# PowerBoard.net
KiCad netlist of a schematic drawn in EAGLE
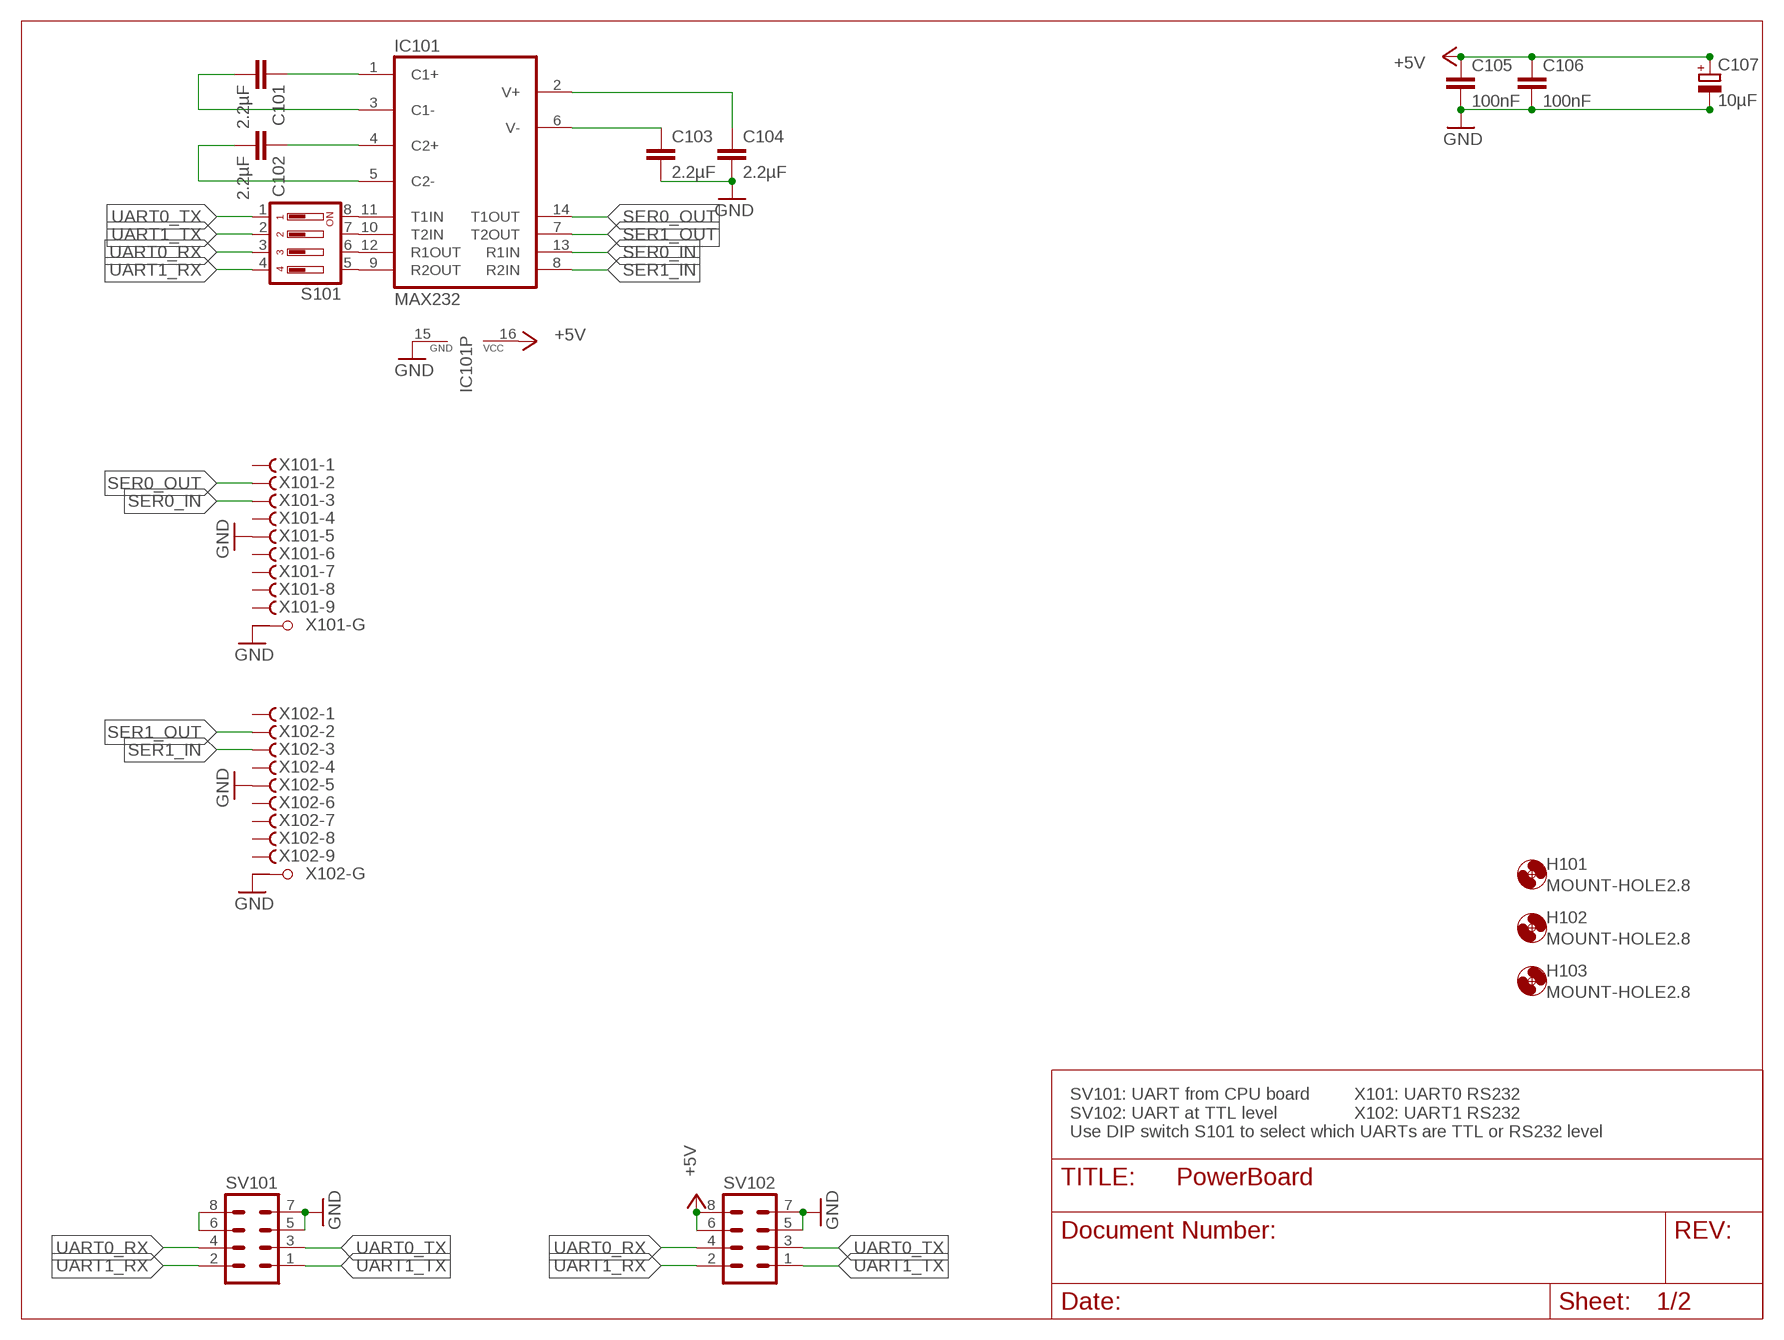
[diagram p0: schematic, sheet 1]
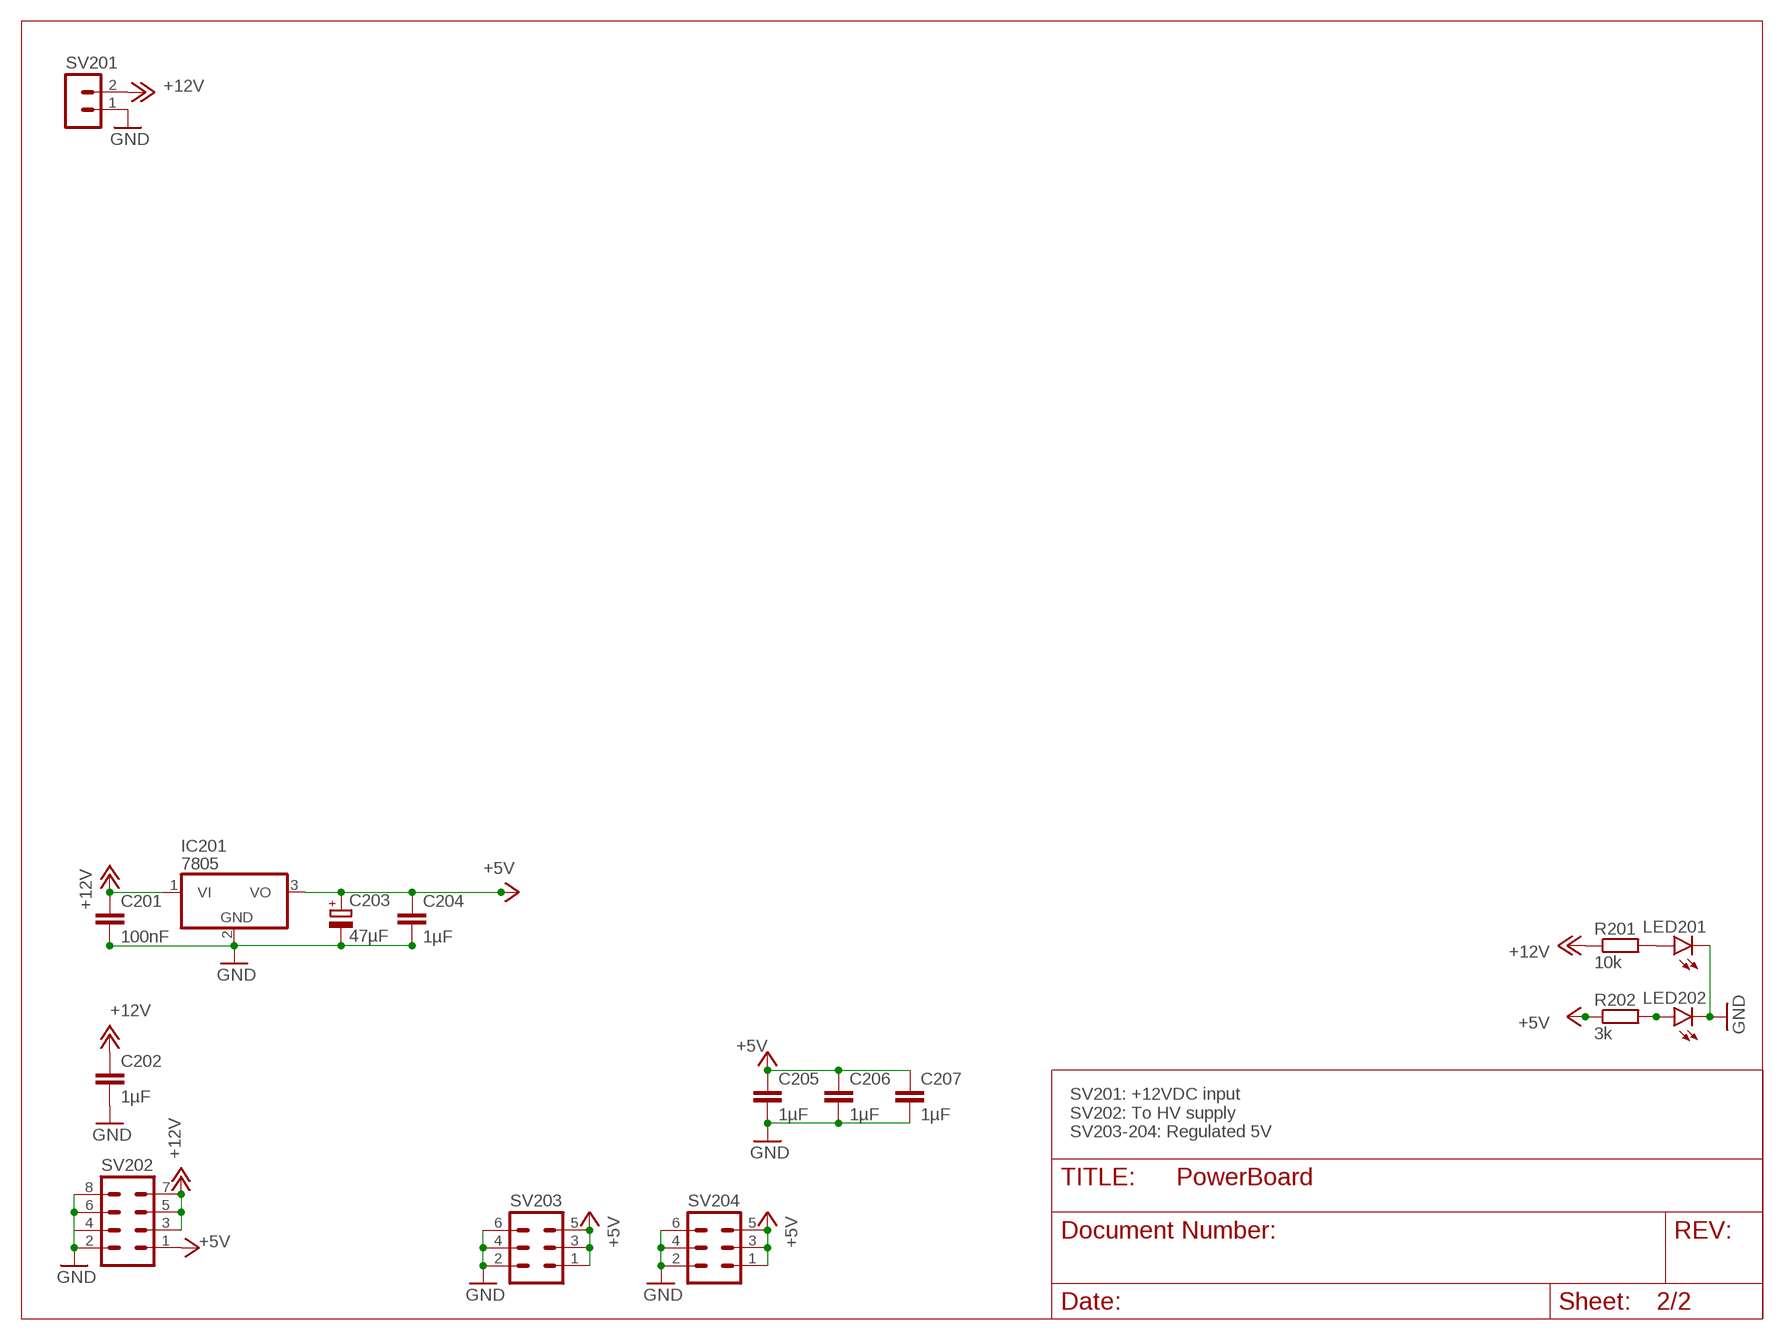
[diagram p1: schematic, sheet 2]

(export (version "E")
  (design (tool "Eeschema 10.0.6"))
  (components
    (comp (ref "C101")
      (value "2.2µF")
      (footprint "eagle-import:C0805")
      (libsource (lib "eagle-import") (part "C-EUC0805"))
    )
    (comp (ref "C102")
      (value "2.2µF")
      (footprint "eagle-import:C0805")
      (libsource (lib "eagle-import") (part "C-EUC0805"))
    )
    (comp (ref "C103")
      (value "2.2µF")
      (footprint "eagle-import:C0805")
      (libsource (lib "eagle-import") (part "C-EUC0805"))
    )
    (comp (ref "C104")
      (value "2.2µF")
      (footprint "eagle-import:C0805")
      (libsource (lib "eagle-import") (part "C-EUC0805"))
    )
    (comp (ref "C105")
      (value "100nF")
      (footprint "eagle-import:C0805")
      (libsource (lib "eagle-import") (part "C-EUC0805"))
    )
    (comp (ref "C106")
      (value "100nF")
      (footprint "eagle-import:C0805")
      (libsource (lib "eagle-import") (part "C-EUC0805"))
    )
    (comp (ref "C107")
      (value "10µF")
      (footprint "eagle-import:SMC_B")
      (libsource (lib "eagle-import") (part "CPOL-EUSMCB"))
    )
    (comp (ref "H101")
      (value "MOUNT-HOLE2.8")
      (footprint "eagle-import:2,8")
      (libsource (lib "eagle-import") (part "MOUNT-HOLE2.8"))
    )
    (comp (ref "H102")
      (value "MOUNT-HOLE2.8")
      (footprint "eagle-import:2,8")
      (libsource (lib "eagle-import") (part "MOUNT-HOLE2.8"))
    )
    (comp (ref "H103")
      (value "MOUNT-HOLE2.8")
      (footprint "eagle-import:2,8")
      (libsource (lib "eagle-import") (part "MOUNT-HOLE2.8"))
    )
    (comp (ref "IC101")
      (value "MAX232")
      (footprint "eagle-import:DIL16")
      (fields
        (field (name "MF") "MAXIM")
        (field (name "MPN") "MAX232ACPE+")
        (field (name "MOUSER") "595-MAX232N")
      )
      (libsource (lib "eagle-import") (part "MAX232"))
    )
    (comp (ref "S101")
      (value "DP04")
      (footprint "eagle-import:DP-04")
      (libsource (lib "eagle-import") (part "DP04"))
    )
    (comp (ref "SV101")
      (value "MA04-2")
      (footprint "eagle-import:MA04-2")
      (libsource (lib "eagle-import") (part "MA04-2"))
    )
    (comp (ref "SV102")
      (value "MA04-2")
      (footprint "eagle-import:MA04-2")
      (libsource (lib "eagle-import") (part "MA04-2"))
    )
    (comp (ref "X101")
      (value "F09HPS")
      (footprint "eagle-import:F09HP")
      (libsource (lib "eagle-import") (part "F09HPS"))
    )
    (comp (ref "X102")
      (value "F09HPS")
      (footprint "eagle-import:F09HP")
      (libsource (lib "eagle-import") (part "F09HPS"))
    )
    (comp (ref "C201")
      (value "100nF")
      (footprint "eagle-import:C0805")
      (libsource (lib "eagle-import") (part "C-EUC0805"))
    )
    (comp (ref "C202")
      (value "1µF")
      (footprint "eagle-import:C0805")
      (libsource (lib "eagle-import") (part "C-EUC0805"))
    )
    (comp (ref "C203")
      (value "47µF")
      (footprint "eagle-import:CT6032")
      (libsource (lib "eagle-import") (part "CPOL-EUCT6032"))
    )
    (comp (ref "C204")
      (value "1µF")
      (footprint "eagle-import:C0805")
      (libsource (lib "eagle-import") (part "C-EUC0805"))
    )
    (comp (ref "C205")
      (value "1µF")
      (footprint "eagle-import:C0805")
      (libsource (lib "eagle-import") (part "C-EUC0805"))
    )
    (comp (ref "C206")
      (value "1µF")
      (footprint "eagle-import:C0805")
      (libsource (lib "eagle-import") (part "C-EUC0805"))
    )
    (comp (ref "C207")
      (value "1µF")
      (footprint "eagle-import:C0805")
      (libsource (lib "eagle-import") (part "C-EUC0805"))
    )
    (comp (ref "IC201")
      (value "7805")
      (footprint "eagle-import:TO220V")
      (libsource (lib "eagle-import") (part "78TV05"))
    )
    (comp (ref "LED201")
      (value "LEDCHIPLED_1206")
      (footprint "eagle-import:CHIPLED_1206")
      (libsource (lib "eagle-import") (part "LEDCHIPLED_1206"))
    )
    (comp (ref "LED202")
      (value "LEDCHIPLED_1206")
      (footprint "eagle-import:CHIPLED_1206")
      (libsource (lib "eagle-import") (part "LEDCHIPLED_1206"))
    )
    (comp (ref "R201")
      (value "10k")
      (footprint "eagle-import:R2012")
      (libsource (lib "eagle-import") (part "R-EU_R2012"))
    )
    (comp (ref "R202")
      (value "3k")
      (footprint "eagle-import:R2012")
      (libsource (lib "eagle-import") (part "R-EU_R2012"))
    )
    (comp (ref "SV201")
      (value "1792863")
      (footprint "eagle-import:1792863")
      (libsource (lib "eagle-import") (part "1792863"))
    )
    (comp (ref "SV202")
      (value "MA04-2")
      (footprint "eagle-import:MA04-2")
      (libsource (lib "eagle-import") (part "MA04-2"))
    )
    (comp (ref "SV203")
      (value "MA03-2")
      (footprint "eagle-import:MA03-2")
      (libsource (lib "eagle-import") (part "MA03-2"))
    )
    (comp (ref "SV204")
      (value "MA03-2")
      (footprint "eagle-import:MA03-2")
      (libsource (lib "eagle-import") (part "MA03-2"))
    )
  )
  (nets
    (net (code "1") (name "+5V") (class "Default")
      (node (ref "C105") (pin "1") (pinfunction "1_1") (pintype "passive"))
      (node (ref "C106") (pin "1") (pinfunction "1_1") (pintype "passive"))
      (node (ref "C107") (pin "+") (pinfunction "+_+") (pintype "passive"))
      (node (ref "C203") (pin "+") (pinfunction "+_+") (pintype "passive"))
      (node (ref "C204") (pin "1") (pinfunction "1_1") (pintype "passive"))
      (node (ref "C205") (pin "1") (pinfunction "1_1") (pintype "passive"))
      (node (ref "C206") (pin "1") (pinfunction "1_1") (pintype "passive"))
      (node (ref "C207") (pin "1") (pinfunction "1_1") (pintype "passive"))
      (node (ref "IC101") (pin "16") (pinfunction "VCC_16") (pintype "power_in"))
      (node (ref "IC201") (pin "3") (pinfunction "VO_3") (pintype "passive"))
      (node (ref "R202") (pin "1") (pinfunction "1_1") (pintype "passive"))
      (node (ref "SV102") (pin "6") (pinfunction "6_6") (pintype "passive"))
      (node (ref "SV102") (pin "8") (pinfunction "8_8") (pintype "passive"))
      (node (ref "SV202") (pin "1") (pinfunction "1_1") (pintype "passive"))
      (node (ref "SV203") (pin "1") (pinfunction "1_1") (pintype "passive"))
      (node (ref "SV203") (pin "3") (pinfunction "3_3") (pintype "passive"))
      (node (ref "SV203") (pin "5") (pinfunction "5_5") (pintype "passive"))
      (node (ref "SV204") (pin "1") (pinfunction "1_1") (pintype "passive"))
      (node (ref "SV204") (pin "3") (pinfunction "3_3") (pintype "passive"))
      (node (ref "SV204") (pin "5") (pinfunction "5_5") (pintype "passive"))
    )
    (net (code "2") (name "+12V") (class "Default")
      (node (ref "C201") (pin "1") (pinfunction "1_1") (pintype "passive"))
      (node (ref "C202") (pin "1") (pinfunction "1_1") (pintype "passive"))
      (node (ref "IC201") (pin "1") (pinfunction "VI_1") (pintype "input"))
      (node (ref "R201") (pin "1") (pinfunction "1_1") (pintype "passive"))
      (node (ref "SV201") (pin "2") (pinfunction "2_2") (pintype "passive"))
      (node (ref "SV202") (pin "3") (pinfunction "3_3") (pintype "passive"))
      (node (ref "SV202") (pin "5") (pinfunction "5_5") (pintype "passive"))
      (node (ref "SV202") (pin "7") (pinfunction "7_7") (pintype "passive"))
    )
    (net (code "3") (name "GND") (class "Default")
      (node (ref "C103") (pin "2") (pinfunction "2_2") (pintype "passive"))
      (node (ref "C104") (pin "2") (pinfunction "2_2") (pintype "passive"))
      (node (ref "C105") (pin "2") (pinfunction "2_2") (pintype "passive"))
      (node (ref "C106") (pin "2") (pinfunction "2_2") (pintype "passive"))
      (node (ref "C107") (pin "-") (pinfunction "-_-") (pintype "passive"))
      (node (ref "C201") (pin "2") (pinfunction "2_2") (pintype "passive"))
      (node (ref "C202") (pin "2") (pinfunction "2_2") (pintype "passive"))
      (node (ref "C203") (pin "-") (pinfunction "-_-") (pintype "passive"))
      (node (ref "C204") (pin "2") (pinfunction "2_2") (pintype "passive"))
      (node (ref "C205") (pin "2") (pinfunction "2_2") (pintype "passive"))
      (node (ref "C206") (pin "2") (pinfunction "2_2") (pintype "passive"))
      (node (ref "C207") (pin "2") (pinfunction "2_2") (pintype "passive"))
      (node (ref "IC101") (pin "15") (pinfunction "GND_15") (pintype "power_in"))
      (node (ref "IC201") (pin "2") (pinfunction "GND_2") (pintype "passive"))
      (node (ref "LED201") (pin "C") (pinfunction "C_C") (pintype "passive"))
      (node (ref "LED202") (pin "C") (pinfunction "C_C") (pintype "passive"))
      (node (ref "SV101") (pin "5") (pinfunction "5_5") (pintype "passive"))
      (node (ref "SV101") (pin "7") (pinfunction "7_7") (pintype "passive"))
      (node (ref "SV102") (pin "5") (pinfunction "5_5") (pintype "passive"))
      (node (ref "SV102") (pin "7") (pinfunction "7_7") (pintype "passive"))
      (node (ref "SV201") (pin "1") (pinfunction "1_1") (pintype "passive"))
      (node (ref "SV202") (pin "2") (pinfunction "2_2") (pintype "passive"))
      (node (ref "SV202") (pin "4") (pinfunction "4_4") (pintype "passive"))
      (node (ref "SV202") (pin "6") (pinfunction "6_6") (pintype "passive"))
      (node (ref "SV202") (pin "8") (pinfunction "8_8") (pintype "passive"))
      (node (ref "SV203") (pin "2") (pinfunction "2_2") (pintype "passive"))
      (node (ref "SV203") (pin "4") (pinfunction "4_4") (pintype "passive"))
      (node (ref "SV203") (pin "6") (pinfunction "6_6") (pintype "passive"))
      (node (ref "SV204") (pin "2") (pinfunction "2_2") (pintype "passive"))
      (node (ref "SV204") (pin "4") (pinfunction "4_4") (pintype "passive"))
      (node (ref "SV204") (pin "6") (pinfunction "6_6") (pintype "passive"))
      (node (ref "X101") (pin "5") (pinfunction "F_5") (pintype "passive"))
      (node (ref "X101") (pin "G1") (pinfunction "G1_G1") (pintype "passive"))
      (node (ref "X102") (pin "5") (pinfunction "F_5") (pintype "passive"))
      (node (ref "X102") (pin "G1") (pinfunction "G1_G1") (pintype "passive"))
    )
    (net (code "4") (name "Net-(IC101A-C1+)") (class "Default")
      (node (ref "C101") (pin "1") (pinfunction "1_1") (pintype "passive"))
      (node (ref "IC101") (pin "1") (pinfunction "C1+_1") (pintype "bidirectional"))
    )
    (net (code "5") (name "Net-(IC101A-C1-)") (class "Default")
      (node (ref "C101") (pin "2") (pinfunction "2_2") (pintype "passive"))
      (node (ref "IC101") (pin "3") (pinfunction "C1-_3") (pintype "bidirectional"))
    )
    (net (code "6") (name "Net-(IC101A-C2+)") (class "Default")
      (node (ref "C102") (pin "1") (pinfunction "1_1") (pintype "passive"))
      (node (ref "IC101") (pin "4") (pinfunction "C2+_4") (pintype "bidirectional"))
    )
    (net (code "7") (name "Net-(IC101A-C2-)") (class "Default")
      (node (ref "C102") (pin "2") (pinfunction "2_2") (pintype "passive"))
      (node (ref "IC101") (pin "5") (pinfunction "C2-_5") (pintype "bidirectional"))
    )
    (net (code "8") (name "Net-(IC101A-R1OUT)") (class "Default")
      (node (ref "IC101") (pin "12") (pinfunction "R1OUT_12") (pintype "output"))
      (node (ref "S101") (pin "6") (pinfunction "6_6") (pintype "passive"))
    )
    (net (code "9") (name "Net-(IC101A-R2OUT)") (class "Default")
      (node (ref "IC101") (pin "9") (pinfunction "R2OUT_9") (pintype "output"))
      (node (ref "S101") (pin "5") (pinfunction "5_5") (pintype "passive"))
    )
    (net (code "10") (name "Net-(IC101A-T1IN)") (class "Default")
      (node (ref "IC101") (pin "11") (pinfunction "T1IN_11") (pintype "input"))
      (node (ref "S101") (pin "8") (pinfunction "8_8") (pintype "passive"))
    )
    (net (code "11") (name "Net-(IC101A-T2IN)") (class "Default")
      (node (ref "IC101") (pin "10") (pinfunction "T2IN_10") (pintype "input"))
      (node (ref "S101") (pin "7") (pinfunction "7_7") (pintype "passive"))
    )
    (net (code "12") (name "Net-(IC101A-V+)") (class "Default")
      (node (ref "C104") (pin "1") (pinfunction "1_1") (pintype "passive"))
      (node (ref "IC101") (pin "2") (pinfunction "V+_2") (pintype "bidirectional"))
    )
    (net (code "13") (name "Net-(IC101A-V-)") (class "Default")
      (node (ref "C103") (pin "1") (pinfunction "1_1") (pintype "passive"))
      (node (ref "IC101") (pin "6") (pinfunction "V-_6") (pintype "bidirectional"))
    )
    (net (code "14") (name "Net-(LED201-PadA)") (class "Default")
      (node (ref "LED201") (pin "A") (pinfunction "A_A") (pintype "passive"))
      (node (ref "R201") (pin "2") (pinfunction "2_2") (pintype "passive"))
    )
    (net (code "15") (name "Net-(LED202-PadA)") (class "Default")
      (node (ref "LED202") (pin "A") (pinfunction "A_A") (pintype "passive"))
      (node (ref "R202") (pin "2") (pinfunction "2_2") (pintype "passive"))
    )
    (net (code "16") (name "Net-(SV101-Pad6)") (class "Default")
      (node (ref "SV101") (pin "6") (pinfunction "6_6") (pintype "passive"))
      (node (ref "SV101") (pin "8") (pinfunction "8_8") (pintype "passive"))
    )
    (net (code "17") (name "SER0_IN") (class "Default")
      (node (ref "IC101") (pin "13") (pinfunction "R1IN_13") (pintype "input"))
      (node (ref "X101") (pin "3") (pinfunction "F_3") (pintype "passive"))
    )
    (net (code "18") (name "SER0_OUT") (class "Default")
      (node (ref "IC101") (pin "14") (pinfunction "T1OUT_14") (pintype "output"))
      (node (ref "X101") (pin "2") (pinfunction "F_2") (pintype "passive"))
    )
    (net (code "19") (name "SER1_IN") (class "Default")
      (node (ref "IC101") (pin "8") (pinfunction "R2IN_8") (pintype "input"))
      (node (ref "X102") (pin "3") (pinfunction "F_3") (pintype "passive"))
    )
    (net (code "20") (name "SER1_OUT") (class "Default")
      (node (ref "IC101") (pin "7") (pinfunction "T2OUT_7") (pintype "output"))
      (node (ref "X102") (pin "2") (pinfunction "F_2") (pintype "passive"))
    )
    (net (code "21") (name "UART0_RX") (class "Default")
      (node (ref "S101") (pin "3") (pinfunction "3_3") (pintype "passive"))
      (node (ref "SV101") (pin "4") (pinfunction "4_4") (pintype "passive"))
      (node (ref "SV102") (pin "4") (pinfunction "4_4") (pintype "passive"))
    )
    (net (code "22") (name "UART0_TX") (class "Default")
      (node (ref "S101") (pin "1") (pinfunction "1_1") (pintype "passive"))
      (node (ref "SV101") (pin "3") (pinfunction "3_3") (pintype "passive"))
      (node (ref "SV102") (pin "3") (pinfunction "3_3") (pintype "passive"))
    )
    (net (code "23") (name "UART1_RX") (class "Default")
      (node (ref "S101") (pin "4") (pinfunction "4_4") (pintype "passive"))
      (node (ref "SV101") (pin "2") (pinfunction "2_2") (pintype "passive"))
      (node (ref "SV102") (pin "2") (pinfunction "2_2") (pintype "passive"))
    )
    (net (code "24") (name "UART1_TX") (class "Default")
      (node (ref "S101") (pin "2") (pinfunction "2_2") (pintype "passive"))
      (node (ref "SV101") (pin "1") (pinfunction "1_1") (pintype "passive"))
      (node (ref "SV102") (pin "1") (pinfunction "1_1") (pintype "passive"))
    )
    (net (code "25") (name "unconnected-(X101-PadG2)") (class "Default")
      (node (ref "X101") (pin "G2") (pinfunction "G2_G2") (pintype "passive"))
    )
    (net (code "26") (name "unconnected-(X101A-F-Pad1)") (class "Default")
      (node (ref "X101") (pin "1") (pinfunction "F_1") (pintype "passive"))
    )
    (net (code "27") (name "unconnected-(X101D-F-Pad4)") (class "Default")
      (node (ref "X101") (pin "4") (pinfunction "F_4") (pintype "passive"))
    )
    (net (code "28") (name "unconnected-(X101F-F-Pad6)") (class "Default")
      (node (ref "X101") (pin "6") (pinfunction "F_6") (pintype "passive"))
    )
    (net (code "29") (name "unconnected-(X101G-F-Pad7)") (class "Default")
      (node (ref "X101") (pin "7") (pinfunction "F_7") (pintype "passive"))
    )
    (net (code "30") (name "unconnected-(X101H-F-Pad8)") (class "Default")
      (node (ref "X101") (pin "8") (pinfunction "F_8") (pintype "passive"))
    )
    (net (code "31") (name "unconnected-(X101I-F-Pad9)") (class "Default")
      (node (ref "X101") (pin "9") (pinfunction "F_9") (pintype "passive"))
    )
    (net (code "32") (name "unconnected-(X102-PadG2)") (class "Default")
      (node (ref "X102") (pin "G2") (pinfunction "G2_G2") (pintype "passive"))
    )
    (net (code "33") (name "unconnected-(X102A-F-Pad1)") (class "Default")
      (node (ref "X102") (pin "1") (pinfunction "F_1") (pintype "passive"))
    )
    (net (code "34") (name "unconnected-(X102D-F-Pad4)") (class "Default")
      (node (ref "X102") (pin "4") (pinfunction "F_4") (pintype "passive"))
    )
    (net (code "35") (name "unconnected-(X102F-F-Pad6)") (class "Default")
      (node (ref "X102") (pin "6") (pinfunction "F_6") (pintype "passive"))
    )
    (net (code "36") (name "unconnected-(X102G-F-Pad7)") (class "Default")
      (node (ref "X102") (pin "7") (pinfunction "F_7") (pintype "passive"))
    )
    (net (code "37") (name "unconnected-(X102H-F-Pad8)") (class "Default")
      (node (ref "X102") (pin "8") (pinfunction "F_8") (pintype "passive"))
    )
    (net (code "38") (name "unconnected-(X102I-F-Pad9)") (class "Default")
      (node (ref "X102") (pin "9") (pinfunction "F_9") (pintype "passive"))
    )
  )
)
